# EasyEDA_Source.net
KiCad netlist of a schematic drawn in EasyEDA
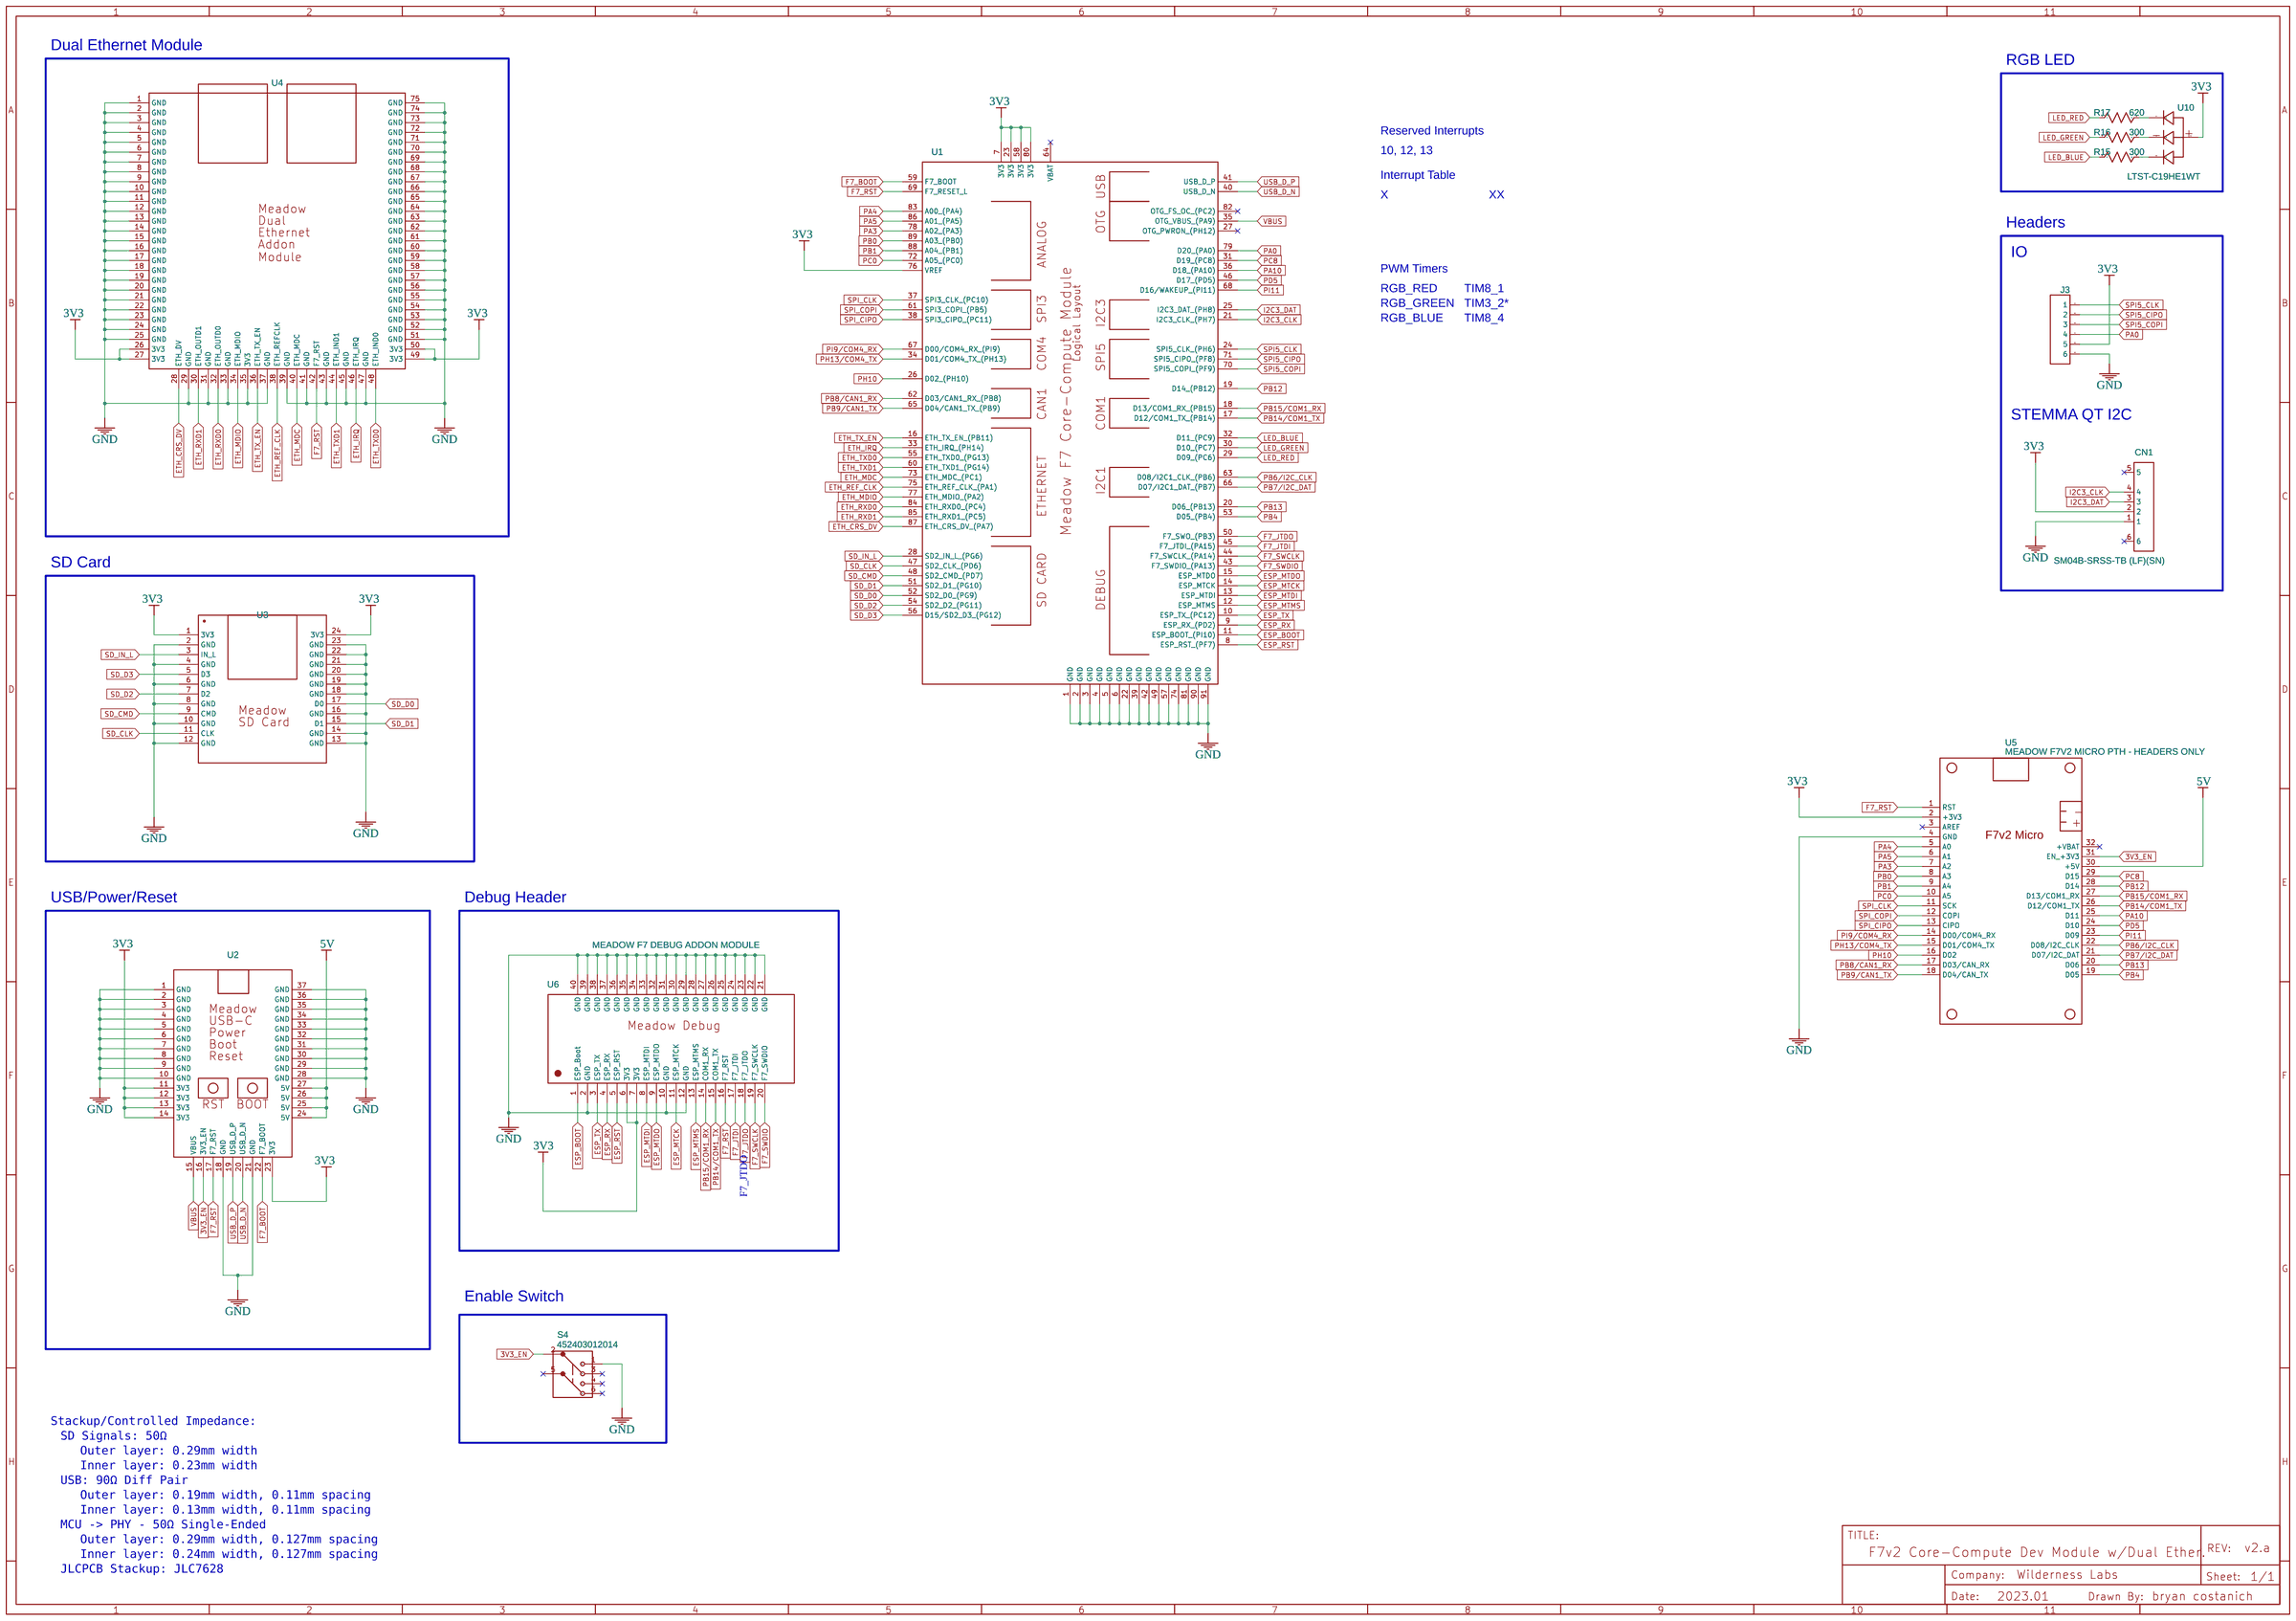
[diagram p0: schematic sheet]

(export (version "E")
  (design (tool "Eeschema 10.0.6"))
  (components
    (comp (ref "CN1")
      (value "SM04B-SRSS-TB (LF)(SN)")
      (fields (field (name "BOM_Supplier Part") "C160404"))
      (libsource (lib "") (part "SM04B-SRSS-TB (LF)(SN)"))
    )
    (comp (ref "J3")
      (value "HDR-M-2.54_1x6")
      (fields (field (name "BOM_Supplier Part") "C190819"))
      (libsource (lib "") (part "HDR-M-2.54_1x6"))
    )
    (comp (ref "R15")
      (value "300")
      (fields (field (name "BOM_Manufacturer Part") "RC0603FR-07300RL"))
      (libsource (lib "") (part "R_0603_US"))
    )
    (comp (ref "R16")
      (value "300")
      (fields (field (name "BOM_Manufacturer Part") "RC0603FR-07300RL"))
      (libsource (lib "") (part "R_0603_US"))
    )
    (comp (ref "R17")
      (value "620")
      (fields (field (name "BOM_Manufacturer Part") "RC0603FR-07620RL"))
      (libsource (lib "") (part "R_0603_US"))
    )
    (comp (ref "S4") (value "452403012014") (libsource (lib "") (part "452403012014")))
    (comp (ref "U1")
      (value "Meadow F7v2 Core-Compute Module - Logical")
      (libsource (lib "") (part "Meadow F7v2 Core-Compute Module - Logical"))
    )
    (comp (ref "U2")
      (value "Meadow Core-Compute USB-C, Power, Boot, and Reset Addon Module")
      (libsource (lib "") (part "Meadow Core-Compute USB-C, Power, Boot, and Reset Addon Module"))
    )
    (comp (ref "U3")
      (value "Meadow Core-Compute SD-Card Addon")
      (libsource (lib "") (part "Meadow Core-Compute SD-Card Addon"))
    )
    (comp (ref "U4")
      (value "MEADOW CORE-COMPUTE DUAL ETHERNET ADDON MODULE")
      (libsource (lib "") (part "MEADOW CORE-COMPUTE DUAL ETHERNET ADDON MODULE"))
    )
    (comp (ref "U5")
      (value "MEADOW F7V2 MICRO PTH - HEADERS ONLY")
      (fields
        (field (name "BOM_Manufacturer Part") "MEDF7DEV")
        (field (name "BOM_Supplier Part") "977-MEADOWF7MICRO")
      )
      (libsource (lib "") (part "MEADOW F7V2 MICRO PTH - HEADERS ONLY"))
    )
    (comp (ref "U6")
      (value "MEADOW F7 DEBUG ADDON MODULE")
      (libsource (lib "") (part "MEADOW F7 DEBUG ADDON MODULE"))
    )
    (comp (ref "U10")
      (value "LTST-C19HE1WT")
      (fields
        (field (name "BOM_Manufacturer Part") "LTST-C19HE1WT-H")
        (field (name "BOM_Supplier Part") "C427425")
      )
      (libsource (lib "") (part "LTST-C19HE1WT-H"))
    )
  )
  (nets
    (net (code "1") (name "3V3") (class "Default")
      (node (ref "CN1") (pin "2") (pinfunction "2_2") (pintype "unspecified"))
      (node (ref "J3") (pin "5") (pinfunction "5_5") (pintype "input"))
      (node (ref "U1") (pin "23") (pinfunction "3V3_23") (pintype "unspecified"))
      (node (ref "U1") (pin "58") (pinfunction "3V3_58") (pintype "passive"))
      (node (ref "U1") (pin "7") (pinfunction "3V3_7") (pintype "unspecified"))
      (node (ref "U1") (pin "76") (pinfunction "VREF_76") (pintype "input"))
      (node (ref "U1") (pin "80") (pinfunction "3V3_80") (pintype "unspecified"))
      (node (ref "U10") (pin "4") (pinfunction "A_4") (pintype "unspecified"))
      (node (ref "U2") (pin "11") (pinfunction "3V3_11") (pintype "unspecified"))
      (node (ref "U2") (pin "12") (pinfunction "3V3_12") (pintype "unspecified"))
      (node (ref "U2") (pin "13") (pinfunction "3V3_13") (pintype "unspecified"))
      (node (ref "U2") (pin "14") (pinfunction "3V3_14") (pintype "unspecified"))
      (node (ref "U2") (pin "23") (pinfunction "3V3_23") (pintype "passive"))
      (node (ref "U3") (pin "1") (pinfunction "3V3_1") (pintype "unspecified"))
      (node (ref "U3") (pin "24") (pinfunction "3V3_24") (pintype "passive"))
      (node (ref "U4") (pin "26") (pinfunction "3V3_26") (pintype "unspecified"))
      (node (ref "U4") (pin "27") (pinfunction "3V3_27") (pintype "unspecified"))
      (node (ref "U4") (pin "49") (pinfunction "3V3_49") (pintype "unspecified"))
      (node (ref "U4") (pin "50") (pinfunction "3V3_50") (pintype "unspecified"))
      (node (ref "U5") (pin "2") (pinfunction "+3V3_2") (pintype "passive"))
      (node (ref "U6") (pin "6") (pinfunction "3V3_6") (pintype "unspecified"))
      (node (ref "U6") (pin "7") (pinfunction "3V3_7") (pintype "unspecified"))
    )
    (net (code "2") (name "3V3_EN") (class "Default")
      (node (ref "S4") (pin "2") (pinfunction "1_2") (pintype "unspecified"))
      (node (ref "U2") (pin "16") (pinfunction "3V3_EN_16") (pintype "unspecified"))
      (node (ref "U5") (pin "31") (pinfunction "EN_+3V3_31") (pintype "unspecified"))
    )
    (net (code "3") (name "5V") (class "Default")
      (node (ref "U2") (pin "24") (pinfunction "5V_24") (pintype "passive"))
      (node (ref "U2") (pin "25") (pinfunction "5V_25") (pintype "passive"))
      (node (ref "U2") (pin "26") (pinfunction "5V_26") (pintype "passive"))
      (node (ref "U2") (pin "27") (pinfunction "5V_27") (pintype "passive"))
      (node (ref "U5") (pin "30") (pinfunction "+5V_30") (pintype "passive"))
    )
    (net (code "4") (name "ESP_BOOT") (class "Default")
      (node (ref "U1") (pin "11") (pinfunction "ESP_BOOT_(PI10)_11") (pintype "unspecified"))
      (node (ref "U6") (pin "1") (pinfunction "ESP_Boot_1") (pintype "unspecified"))
    )
    (net (code "5") (name "ESP_MTCK") (class "Default")
      (node (ref "U1") (pin "14") (pinfunction "ESP_MTCK_14") (pintype "unspecified"))
      (node (ref "U6") (pin "11") (pinfunction "ESP_MTCK_11") (pintype "unspecified"))
    )
    (net (code "6") (name "ESP_MTDI") (class "Default")
      (node (ref "U1") (pin "13") (pinfunction "ESP_MTDI_13") (pintype "unspecified"))
      (node (ref "U6") (pin "8") (pinfunction "ESP_MTDI_8") (pintype "unspecified"))
    )
    (net (code "7") (name "ESP_MTDO") (class "Default")
      (node (ref "U1") (pin "15") (pinfunction "ESP_MTDO_15") (pintype "unspecified"))
      (node (ref "U6") (pin "9") (pinfunction "ESP_MTDO_9") (pintype "unspecified"))
    )
    (net (code "8") (name "ESP_MTMS") (class "Default")
      (node (ref "U1") (pin "12") (pinfunction "ESP_MTMS_12") (pintype "unspecified"))
      (node (ref "U6") (pin "13") (pinfunction "ESP_MTMS_13") (pintype "unspecified"))
    )
    (net (code "9") (name "ESP_RST") (class "Default")
      (node (ref "U1") (pin "8") (pinfunction "ESP_RST_(PF7)_8") (pintype "unspecified"))
      (node (ref "U6") (pin "5") (pinfunction "ESP_RST_5") (pintype "unspecified"))
    )
    (net (code "10") (name "ESP_RX") (class "Default")
      (node (ref "U1") (pin "9") (pinfunction "ESP_RX_(PD2)_9") (pintype "unspecified"))
      (node (ref "U6") (pin "4") (pinfunction "ESP_RX_4") (pintype "unspecified"))
    )
    (net (code "11") (name "ESP_TX") (class "Default")
      (node (ref "U1") (pin "10") (pinfunction "ESP_TX_(PC12)_10") (pintype "unspecified"))
      (node (ref "U6") (pin "3") (pinfunction "ESP_TX_3") (pintype "unspecified"))
    )
    (net (code "12") (name "ETH_CRS_DV") (class "Default")
      (node (ref "U1") (pin "87") (pinfunction "ETH_CRS_DV_(PA7)_87") (pintype "unspecified"))
      (node (ref "U4") (pin "28") (pinfunction "ETH_DV_28") (pintype "unspecified"))
    )
    (net (code "13") (name "ETH_IRQ") (class "Default")
      (node (ref "U1") (pin "33") (pinfunction "ETH_IRQ_(PH14)_33") (pintype "unspecified"))
      (node (ref "U4") (pin "46") (pinfunction "ETH_IRQ_46") (pintype "unspecified"))
    )
    (net (code "14") (name "ETH_MDC") (class "Default")
      (node (ref "U1") (pin "73") (pinfunction "ETH_MDC_(PC1)_73") (pintype "unspecified"))
      (node (ref "U4") (pin "40") (pinfunction "ETH_MDC_40") (pintype "unspecified"))
    )
    (net (code "15") (name "ETH_MDIO") (class "Default")
      (node (ref "U1") (pin "77") (pinfunction "ETH_MDIO_(PA2)_77") (pintype "unspecified"))
      (node (ref "U4") (pin "34") (pinfunction "ETH_MDIO_34") (pintype "unspecified"))
    )
    (net (code "16") (name "ETH_REF_CLK") (class "Default")
      (node (ref "U1") (pin "75") (pinfunction "ETH_REF_CLK_(PA1)_75") (pintype "unspecified"))
      (node (ref "U4") (pin "38") (pinfunction "ETH_REFCLK_38") (pintype "unspecified"))
    )
    (net (code "17") (name "ETH_RXD0") (class "Default")
      (node (ref "U1") (pin "84") (pinfunction "ETH_RXD0_(PC4)_84") (pintype "unspecified"))
      (node (ref "U4") (pin "32") (pinfunction "ETH_OUTD0_32") (pintype "unspecified"))
    )
    (net (code "18") (name "ETH_RXD1") (class "Default")
      (node (ref "U1") (pin "85") (pinfunction "ETH_RXD1_(PC5)_85") (pintype "unspecified"))
      (node (ref "U4") (pin "30") (pinfunction "ETH_OUTD1_30") (pintype "unspecified"))
    )
    (net (code "19") (name "ETH_TXD0") (class "Default")
      (node (ref "U1") (pin "55") (pinfunction "ETH_TXD0_(PG13)_55") (pintype "unspecified"))
      (node (ref "U4") (pin "48") (pinfunction "ETH_IND0_48") (pintype "unspecified"))
    )
    (net (code "20") (name "ETH_TXD1") (class "Default")
      (node (ref "U1") (pin "60") (pinfunction "ETH_TXD1_(PG14)_60") (pintype "unspecified"))
      (node (ref "U4") (pin "44") (pinfunction "ETH_IND1_44") (pintype "unspecified"))
    )
    (net (code "21") (name "ETH_TX_EN") (class "Default")
      (node (ref "U1") (pin "16") (pinfunction "ETH_TX_EN_(PB11)_16") (pintype "unspecified"))
      (node (ref "U4") (pin "36") (pinfunction "ETH_TX_EN_36") (pintype "unspecified"))
    )
    (net (code "22") (name "F7_BOOT") (class "Default")
      (node (ref "U1") (pin "59") (pinfunction "F7_BOOT_59") (pintype "unspecified"))
      (node (ref "U2") (pin "22") (pinfunction "F7_BOOT_22") (pintype "unspecified"))
    )
    (net (code "23") (name "F7_JTDI") (class "Default")
      (node (ref "U1") (pin "45") (pinfunction "F7_JTDI_(PA15)_45") (pintype "unspecified"))
      (node (ref "U6") (pin "17") (pinfunction "F7_JTDI_17") (pintype "unspecified"))
    )
    (net (code "24") (name "F7_JTDO") (class "Default")
      (node (ref "U1") (pin "50") (pinfunction "F7_SWO_(PB3)_50") (pintype "unspecified"))
      (node (ref "U6") (pin "18") (pinfunction "F7_JTDO_18") (pintype "unspecified"))
    )
    (net (code "25") (name "F7_RST") (class "Default")
      (node (ref "U1") (pin "69") (pinfunction "F7_RESET_L_69") (pintype "unspecified"))
      (node (ref "U2") (pin "17") (pinfunction "F7_RST_17") (pintype "unspecified"))
      (node (ref "U4") (pin "42") (pinfunction "F7_RST_42") (pintype "unspecified"))
      (node (ref "U5") (pin "1") (pinfunction "RST_1") (pintype "input"))
      (node (ref "U6") (pin "16") (pinfunction "F7_RST_16") (pintype "unspecified"))
    )
    (net (code "26") (name "F7_SWCLK") (class "Default")
      (node (ref "U1") (pin "44") (pinfunction "F7_SWCLK_(PA14)_44") (pintype "unspecified"))
      (node (ref "U6") (pin "19") (pinfunction "F7_SWCLK_19") (pintype "unspecified"))
    )
    (net (code "27") (name "F7_SWDIO") (class "Default")
      (node (ref "U1") (pin "43") (pinfunction "F7_SWDIO_(PA13)_43") (pintype "unspecified"))
      (node (ref "U6") (pin "20") (pinfunction "F7_SWDIO_20") (pintype "unspecified"))
    )
    (net (code "28") (name "GND") (class "Default")
      (node (ref "CN1") (pin "1") (pinfunction "1_1") (pintype "unspecified"))
      (node (ref "J3") (pin "6") (pinfunction "6_6") (pintype "input"))
      (node (ref "S4") (pin "1") (pinfunction "1_1") (pintype "unspecified"))
      (node (ref "U1") (pin "1") (pinfunction "GND_1") (pintype "passive"))
      (node (ref "U1") (pin "2") (pinfunction "GND_2") (pintype "passive"))
      (node (ref "U1") (pin "22") (pinfunction "GND_22") (pintype "passive"))
      (node (ref "U1") (pin "3") (pinfunction "GND_3") (pintype "passive"))
      (node (ref "U1") (pin "39") (pinfunction "GND_39") (pintype "passive"))
      (node (ref "U1") (pin "4") (pinfunction "GND_4") (pintype "passive"))
      (node (ref "U1") (pin "42") (pinfunction "GND_42") (pintype "passive"))
      (node (ref "U1") (pin "49") (pinfunction "GND_49") (pintype "passive"))
      (node (ref "U1") (pin "5") (pinfunction "GND_5") (pintype "passive"))
      (node (ref "U1") (pin "57") (pinfunction "GND_57") (pintype "passive"))
      (node (ref "U1") (pin "6") (pinfunction "GND_6") (pintype "passive"))
      (node (ref "U1") (pin "74") (pinfunction "GND_74") (pintype "passive"))
      (node (ref "U1") (pin "81") (pinfunction "GND_81") (pintype "passive"))
      (node (ref "U1") (pin "90") (pinfunction "GND_90") (pintype "passive"))
      (node (ref "U1") (pin "91") (pinfunction "GND_91") (pintype "passive"))
      (node (ref "U2") (pin "1") (pinfunction "GND_1") (pintype "unspecified"))
      (node (ref "U2") (pin "10") (pinfunction "GND_10") (pintype "unspecified"))
      (node (ref "U2") (pin "18") (pinfunction "GND_18") (pintype "unspecified"))
      (node (ref "U2") (pin "2") (pinfunction "GND_2") (pintype "unspecified"))
      (node (ref "U2") (pin "21") (pinfunction "GND_21") (pintype "unspecified"))
      (node (ref "U2") (pin "28") (pinfunction "GND_28") (pintype "unspecified"))
      (node (ref "U2") (pin "29") (pinfunction "GND_29") (pintype "unspecified"))
      (node (ref "U2") (pin "3") (pinfunction "GND_3") (pintype "unspecified"))
      (node (ref "U2") (pin "30") (pinfunction "GND_30") (pintype "unspecified"))
      (node (ref "U2") (pin "31") (pinfunction "GND_31") (pintype "unspecified"))
      (node (ref "U2") (pin "32") (pinfunction "GND_32") (pintype "unspecified"))
      (node (ref "U2") (pin "33") (pinfunction "GND_33") (pintype "unspecified"))
      (node (ref "U2") (pin "34") (pinfunction "GND_34") (pintype "unspecified"))
      (node (ref "U2") (pin "35") (pinfunction "GND_35") (pintype "unspecified"))
      (node (ref "U2") (pin "36") (pinfunction "GND_36") (pintype "unspecified"))
      (node (ref "U2") (pin "37") (pinfunction "GND_37") (pintype "unspecified"))
      (node (ref "U2") (pin "4") (pinfunction "GND_4") (pintype "unspecified"))
      (node (ref "U2") (pin "5") (pinfunction "GND_5") (pintype "unspecified"))
      (node (ref "U2") (pin "6") (pinfunction "GND_6") (pintype "unspecified"))
      (node (ref "U2") (pin "7") (pinfunction "GND_7") (pintype "unspecified"))
      (node (ref "U2") (pin "8") (pinfunction "GND_8") (pintype "unspecified"))
      (node (ref "U2") (pin "9") (pinfunction "GND_9") (pintype "unspecified"))
      (node (ref "U3") (pin "10") (pinfunction "GND_10") (pintype "unspecified"))
      (node (ref "U3") (pin "12") (pinfunction "GND_12") (pintype "unspecified"))
      (node (ref "U3") (pin "13") (pinfunction "GND_13") (pintype "unspecified"))
      (node (ref "U3") (pin "14") (pinfunction "GND_14") (pintype "unspecified"))
      (node (ref "U3") (pin "16") (pinfunction "GND_16") (pintype "passive"))
      (node (ref "U3") (pin "18") (pinfunction "GND_18") (pintype "passive"))
      (node (ref "U3") (pin "19") (pinfunction "GND_19") (pintype "passive"))
      (node (ref "U3") (pin "2") (pinfunction "GND_2") (pintype "unspecified"))
      (node (ref "U3") (pin "20") (pinfunction "GND_20") (pintype "passive"))
      (node (ref "U3") (pin "21") (pinfunction "GND_21") (pintype "passive"))
      (node (ref "U3") (pin "22") (pinfunction "GND_22") (pintype "passive"))
      (node (ref "U3") (pin "23") (pinfunction "GND_23") (pintype "passive"))
      (node (ref "U3") (pin "4") (pinfunction "GND_4") (pintype "unspecified"))
      (node (ref "U3") (pin "6") (pinfunction "GND_6") (pintype "unspecified"))
      (node (ref "U3") (pin "8") (pinfunction "GND_8") (pintype "unspecified"))
      (node (ref "U4") (pin "1") (pinfunction "GND_1") (pintype "unspecified"))
      (node (ref "U4") (pin "10") (pinfunction "GND_10") (pintype "unspecified"))
      (node (ref "U4") (pin "11") (pinfunction "GND_11") (pintype "unspecified"))
      (node (ref "U4") (pin "12") (pinfunction "GND_12") (pintype "unspecified"))
      (node (ref "U4") (pin "13") (pinfunction "GND_13") (pintype "unspecified"))
      (node (ref "U4") (pin "14") (pinfunction "GND_14") (pintype "unspecified"))
      (node (ref "U4") (pin "15") (pinfunction "GND_15") (pintype "unspecified"))
      (node (ref "U4") (pin "16") (pinfunction "GND_16") (pintype "unspecified"))
      (node (ref "U4") (pin "17") (pinfunction "GND_17") (pintype "unspecified"))
      (node (ref "U4") (pin "18") (pinfunction "GND_18") (pintype "unspecified"))
      (node (ref "U4") (pin "19") (pinfunction "GND_19") (pintype "unspecified"))
      (node (ref "U4") (pin "2") (pinfunction "GND_2") (pintype "unspecified"))
      (node (ref "U4") (pin "20") (pinfunction "GND_20") (pintype "unspecified"))
      (node (ref "U4") (pin "21") (pinfunction "GND_21") (pintype "unspecified"))
      (node (ref "U4") (pin "22") (pinfunction "GND_22") (pintype "unspecified"))
      (node (ref "U4") (pin "23") (pinfunction "GND_23") (pintype "unspecified"))
      (node (ref "U4") (pin "24") (pinfunction "GND_24") (pintype "unspecified"))
      (node (ref "U4") (pin "25") (pinfunction "GND_25") (pintype "unspecified"))
      (node (ref "U4") (pin "29") (pinfunction "GND_29") (pintype "unspecified"))
      (node (ref "U4") (pin "3") (pinfunction "GND_3") (pintype "unspecified"))
      (node (ref "U4") (pin "31") (pinfunction "GND_31") (pintype "unspecified"))
      (node (ref "U4") (pin "33") (pinfunction "GND_33") (pintype "unspecified"))
      (node (ref "U4") (pin "35") (pinfunction "3V3_35") (pintype "unspecified"))
      (node (ref "U4") (pin "37") (pinfunction "GND_37") (pintype "unspecified"))
      (node (ref "U4") (pin "39") (pinfunction "GND_39") (pintype "unspecified"))
      (node (ref "U4") (pin "4") (pinfunction "GND_4") (pintype "unspecified"))
      (node (ref "U4") (pin "41") (pinfunction "GND_41") (pintype "unspecified"))
      (node (ref "U4") (pin "43") (pinfunction "GND_43") (pintype "unspecified"))
      (node (ref "U4") (pin "45") (pinfunction "GND_45") (pintype "unspecified"))
      (node (ref "U4") (pin "47") (pinfunction "GND_47") (pintype "unspecified"))
      (node (ref "U4") (pin "5") (pinfunction "GND_5") (pintype "unspecified"))
      (node (ref "U4") (pin "51") (pinfunction "GND_51") (pintype "unspecified"))
      (node (ref "U4") (pin "52") (pinfunction "GND_52") (pintype "unspecified"))
      (node (ref "U4") (pin "53") (pinfunction "GND_53") (pintype "unspecified"))
      (node (ref "U4") (pin "54") (pinfunction "GND_54") (pintype "unspecified"))
      (node (ref "U4") (pin "55") (pinfunction "GND_55") (pintype "unspecified"))
      (node (ref "U4") (pin "56") (pinfunction "GND_56") (pintype "unspecified"))
      (node (ref "U4") (pin "57") (pinfunction "GND_57") (pintype "unspecified"))
      (node (ref "U4") (pin "58") (pinfunction "GND_58") (pintype "unspecified"))
      (node (ref "U4") (pin "59") (pinfunction "GND_59") (pintype "unspecified"))
      (node (ref "U4") (pin "6") (pinfunction "GND_6") (pintype "unspecified"))
      (node (ref "U4") (pin "60") (pinfunction "GND_60") (pintype "unspecified"))
      (node (ref "U4") (pin "61") (pinfunction "GND_61") (pintype "unspecified"))
      (node (ref "U4") (pin "62") (pinfunction "GND_62") (pintype "unspecified"))
      (node (ref "U4") (pin "63") (pinfunction "GND_63") (pintype "unspecified"))
      (node (ref "U4") (pin "64") (pinfunction "GND_64") (pintype "unspecified"))
      (node (ref "U4") (pin "65") (pinfunction "GND_65") (pintype "unspecified"))
      (node (ref "U4") (pin "66") (pinfunction "GND_66") (pintype "unspecified"))
      (node (ref "U4") (pin "67") (pinfunction "GND_67") (pintype "unspecified"))
      (node (ref "U4") (pin "68") (pinfunction "GND_68") (pintype "unspecified"))
      (node (ref "U4") (pin "69") (pinfunction "GND_69") (pintype "unspecified"))
      (node (ref "U4") (pin "7") (pinfunction "GND_7") (pintype "unspecified"))
      (node (ref "U4") (pin "70") (pinfunction "GND_70") (pintype "unspecified"))
      (node (ref "U4") (pin "71") (pinfunction "GND_71") (pintype "unspecified"))
      (node (ref "U4") (pin "72") (pinfunction "GND_72") (pintype "unspecified"))
      (node (ref "U4") (pin "73") (pinfunction "GND_73") (pintype "unspecified"))
      (node (ref "U4") (pin "74") (pinfunction "GND_74") (pintype "unspecified"))
      (node (ref "U4") (pin "75") (pinfunction "GND_75") (pintype "unspecified"))
      (node (ref "U4") (pin "8") (pinfunction "GND_8") (pintype "unspecified"))
      (node (ref "U4") (pin "9") (pinfunction "GND_9") (pintype "unspecified"))
      (node (ref "U5") (pin "4") (pinfunction "GND_4") (pintype "passive"))
      (node (ref "U6") (pin "10") (pinfunction "GND_10") (pintype "unspecified"))
      (node (ref "U6") (pin "12") (pinfunction "GND_12") (pintype "unspecified"))
      (node (ref "U6") (pin "2") (pinfunction "GND_2") (pintype "unspecified"))
      (node (ref "U6") (pin "21") (pinfunction "GND_21") (pintype "unspecified"))
      (node (ref "U6") (pin "22") (pinfunction "GND_22") (pintype "unspecified"))
      (node (ref "U6") (pin "23") (pinfunction "GND_23") (pintype "unspecified"))
      (node (ref "U6") (pin "24") (pinfunction "GND_24") (pintype "unspecified"))
      (node (ref "U6") (pin "25") (pinfunction "GND_25") (pintype "unspecified"))
      (node (ref "U6") (pin "26") (pinfunction "GND_26") (pintype "unspecified"))
      (node (ref "U6") (pin "27") (pinfunction "GND_27") (pintype "unspecified"))
      (node (ref "U6") (pin "28") (pinfunction "GND_28") (pintype "unspecified"))
      (node (ref "U6") (pin "29") (pinfunction "GND_29") (pintype "unspecified"))
      (node (ref "U6") (pin "30") (pinfunction "GND_30") (pintype "unspecified"))
      (node (ref "U6") (pin "31") (pinfunction "GND_31") (pintype "unspecified"))
      (node (ref "U6") (pin "32") (pinfunction "GND_32") (pintype "unspecified"))
      (node (ref "U6") (pin "33") (pinfunction "GND_33") (pintype "unspecified"))
      (node (ref "U6") (pin "34") (pinfunction "GND_34") (pintype "unspecified"))
      (node (ref "U6") (pin "35") (pinfunction "GND_35") (pintype "unspecified"))
      (node (ref "U6") (pin "36") (pinfunction "GND_36") (pintype "unspecified"))
      (node (ref "U6") (pin "37") (pinfunction "GND_37") (pintype "unspecified"))
      (node (ref "U6") (pin "38") (pinfunction "GND_38") (pintype "unspecified"))
      (node (ref "U6") (pin "39") (pinfunction "GND_39") (pintype "unspecified"))
      (node (ref "U6") (pin "40") (pinfunction "GND_40") (pintype "unspecified"))
    )
    (net (code "29") (name "I2C3_CLK") (class "Default")
      (node (ref "CN1") (pin "4") (pinfunction "4_4") (pintype "unspecified"))
      (node (ref "U1") (pin "21") (pinfunction "I2C3_CLK_(PH7)_21") (pintype "unspecified"))
    )
    (net (code "30") (name "I2C3_DAT") (class "Default")
      (node (ref "CN1") (pin "3") (pinfunction "3_3") (pintype "unspecified"))
      (node (ref "U1") (pin "25") (pinfunction "I2C3_DAT_(PH8)_25") (pintype "unspecified"))
    )
    (net (code "31") (name "LED_BLUE") (class "Default")
      (node (ref "R15") (pin "1") (pinfunction "1_1") (pintype "unspecified"))
      (node (ref "U1") (pin "32") (pinfunction "D11_(PC9)_32") (pintype "unspecified"))
    )
    (net (code "32") (name "LED_GREEN") (class "Default")
      (node (ref "R16") (pin "1") (pinfunction "1_1") (pintype "unspecified"))
      (node (ref "U1") (pin "30") (pinfunction "D10_(PC7)_30") (pintype "unspecified"))
    )
    (net (code "33") (name "LED_RED") (class "Default")
      (node (ref "R17") (pin "1") (pinfunction "1_1") (pintype "unspecified"))
      (node (ref "U1") (pin "29") (pinfunction "D09_(PC6)_29") (pintype "unspecified"))
    )
    (net (code "34") (name "Net-(U10-C1)") (class "Default")
      (node (ref "R17") (pin "2") (pinfunction "2_2") (pintype "unspecified"))
      (node (ref "U10") (pin "1") (pinfunction "C1_1") (pintype "unspecified"))
    )
    (net (code "35") (name "Net-(U10-C2)") (class "Default")
      (node (ref "R16") (pin "2") (pinfunction "2_2") (pintype "unspecified"))
      (node (ref "U10") (pin "2") (pinfunction "C2_2") (pintype "unspecified"))
    )
    (net (code "36") (name "Net-(U10-C3)") (class "Default")
      (node (ref "R15") (pin "2") (pinfunction "2_2") (pintype "unspecified"))
      (node (ref "U10") (pin "3") (pinfunction "C3_3") (pintype "unspecified"))
    )
    (net (code "37") (name "PA0") (class "Default")
      (node (ref "J3") (pin "4") (pinfunction "4_4") (pintype "input"))
      (node (ref "U1") (pin "79") (pinfunction "D20_(PA0)_79") (pintype "unspecified"))
    )
    (net (code "38") (name "PA3") (class "Default")
      (node (ref "U1") (pin "78") (pinfunction "A02_(PA3)_78") (pintype "unspecified"))
      (node (ref "U5") (pin "7") (pinfunction "A2_7") (pintype "bidirectional"))
    )
    (net (code "39") (name "PA4") (class "Default")
      (node (ref "U1") (pin "83") (pinfunction "A00_(PA4)_83") (pintype "unspecified"))
      (node (ref "U5") (pin "5") (pinfunction "A0_5") (pintype "bidirectional"))
    )
    (net (code "40") (name "PA5") (class "Default")
      (node (ref "U1") (pin "86") (pinfunction "A01_(PA5)_86") (pintype "unspecified"))
      (node (ref "U5") (pin "6") (pinfunction "A1_6") (pintype "bidirectional"))
    )
    (net (code "41") (name "PA10") (class "Default")
      (node (ref "U1") (pin "36") (pinfunction "D18_(PA10)_36") (pintype "unspecified"))
      (node (ref "U5") (pin "25") (pinfunction "D11_25") (pintype "bidirectional"))
    )
    (net (code "42") (name "PB0") (class "Default")
      (node (ref "U1") (pin "89") (pinfunction "A03_(PB0)_89") (pintype "unspecified"))
      (node (ref "U5") (pin "8") (pinfunction "A3_8") (pintype "bidirectional"))
    )
    (net (code "43") (name "PB1") (class "Default")
      (node (ref "U1") (pin "88") (pinfunction "A04_(PB1)_88") (pintype "unspecified"))
      (node (ref "U5") (pin "9") (pinfunction "A4_9") (pintype "bidirectional"))
    )
    (net (code "44") (name "PB4") (class "Default")
      (node (ref "U1") (pin "53") (pinfunction "D05_(PB4)_53") (pintype "unspecified"))
      (node (ref "U5") (pin "19") (pinfunction "D05_19") (pintype "bidirectional"))
    )
    (net (code "45") (name "PB6{slash}I2C_CLK") (class "Default")
      (node (ref "U1") (pin "63") (pinfunction "D08/I2C1_CLK_(PB6)_63") (pintype "unspecified"))
      (node (ref "U5") (pin "22") (pinfunction "D08/I2C_CLK_22") (pintype "bidirectional"))
    )
    (net (code "46") (name "PB7{slash}I2C_DAT") (class "Default")
      (node (ref "U1") (pin "66") (pinfunction "D07/I2C1_DAT_(PB7)_66") (pintype "unspecified"))
      (node (ref "U5") (pin "21") (pinfunction "D07/I2C_DAT_21") (pintype "bidirectional"))
    )
    (net (code "47") (name "PB8{slash}CAN1_RX") (class "Default")
      (node (ref "U1") (pin "62") (pinfunction "D03/CAN1_RX_(PB8)_62") (pintype "unspecified"))
      (node (ref "U5") (pin "17") (pinfunction "D03/CAN_RX_17") (pintype "bidirectional"))
    )
    (net (code "48") (name "PB9{slash}CAN1_TX") (class "Default")
      (node (ref "U1") (pin "65") (pinfunction "D04/CAN1_TX_(PB9)_65") (pintype "unspecified"))
      (node (ref "U5") (pin "18") (pinfunction "D04/CAN_TX_18") (pintype "bidirectional"))
    )
    (net (code "49") (name "PB12") (class "Default")
      (node (ref "U1") (pin "19") (pinfunction "D14_(PB12)_19") (pintype "unspecified"))
      (node (ref "U5") (pin "28") (pinfunction "D14_28") (pintype "bidirectional"))
    )
    (net (code "50") (name "PB13") (class "Default")
      (node (ref "U1") (pin "20") (pinfunction "D06_(PB13)_20") (pintype "unspecified"))
      (node (ref "U5") (pin "20") (pinfunction "D06_20") (pintype "bidirectional"))
    )
    (net (code "51") (name "PB14{slash}COM1_TX") (class "Default")
      (node (ref "U1") (pin "17") (pinfunction "D12/COM1_TX_(PB14)_17") (pintype "unspecified"))
      (node (ref "U5") (pin "26") (pinfunction "D12/COM1_TX_26") (pintype "bidirectional"))
      (node (ref "U6") (pin "15") (pinfunction "COM1_TX_15") (pintype "unspecified"))
    )
    (net (code "52") (name "PB15{slash}COM1_RX") (class "Default")
      (node (ref "U1") (pin "18") (pinfunction "D13/COM1_RX_(PB15)_18") (pintype "unspecified"))
      (node (ref "U5") (pin "27") (pinfunction "D13/COM1_RX_27") (pintype "bidirectional"))
      (node (ref "U6") (pin "14") (pinfunction "COM1_RX_14") (pintype "unspecified"))
    )
    (net (code "53") (name "PC0") (class "Default")
      (node (ref "U1") (pin "72") (pinfunction "A05_(PC0)_72") (pintype "unspecified"))
      (node (ref "U5") (pin "10") (pinfunction "A5_10") (pintype "bidirectional"))
    )
    (net (code "54") (name "PC8") (class "Default")
      (node (ref "U1") (pin "31") (pinfunction "D19_(PC8)_31") (pintype "unspecified"))
      (node (ref "U5") (pin "29") (pinfunction "D15_29") (pintype "bidirectional"))
    )
    (net (code "55") (name "PD5") (class "Default")
      (node (ref "U1") (pin "46") (pinfunction "D17_(PD5)_46") (pintype "unspecified"))
      (node (ref "U5") (pin "24") (pinfunction "D10_24") (pintype "bidirectional"))
    )
    (net (code "56") (name "PH10") (class "Default")
      (node (ref "U1") (pin "26") (pinfunction "D02_(PH10)_26") (pintype "unspecified"))
      (node (ref "U5") (pin "16") (pinfunction "D02_16") (pintype "bidirectional"))
    )
    (net (code "57") (name "PH13{slash}COM4_TX") (class "Default")
      (node (ref "U1") (pin "34") (pinfunction "D01/COM4_TX_(PH13)_34") (pintype "unspecified"))
      (node (ref "U5") (pin "15") (pinfunction "D01/COM4_TX_15") (pintype "bidirectional"))
    )
    (net (code "58") (name "PI9{slash}COM4_RX") (class "Default")
      (node (ref "U1") (pin "67") (pinfunction "D00/COM4_RX_(PI9)_67") (pintype "unspecified"))
      (node (ref "U5") (pin "14") (pinfunction "D00/COM4_RX_14") (pintype "bidirectional"))
    )
    (net (code "59") (name "PI11") (class "Default")
      (node (ref "U1") (pin "68") (pinfunction "D16/WAKEUP_(PI11)_68") (pintype "unspecified"))
      (node (ref "U5") (pin "23") (pinfunction "D09_23") (pintype "bidirectional"))
    )
    (net (code "60") (name "SD_CLK") (class "Default")
      (node (ref "U1") (pin "47") (pinfunction "SD2_CLK_(PD6)_47") (pintype "unspecified"))
      (node (ref "U3") (pin "11") (pinfunction "CLK_11") (pintype "unspecified"))
    )
    (net (code "61") (name "SD_CMD") (class "Default")
      (node (ref "U1") (pin "48") (pinfunction "SD2_CMD_(PD7)_48") (pintype "unspecified"))
      (node (ref "U3") (pin "9") (pinfunction "CMD_9") (pintype "unspecified"))
    )
    (net (code "62") (name "SD_D0") (class "Default")
      (node (ref "U1") (pin "52") (pinfunction "SD2_D0_(PG9)_52") (pintype "unspecified"))
      (node (ref "U3") (pin "17") (pinfunction "D0_17") (pintype "passive"))
    )
    (net (code "63") (name "SD_D1") (class "Default")
      (node (ref "U1") (pin "51") (pinfunction "SD2_D1_(PG10)_51") (pintype "unspecified"))
      (node (ref "U3") (pin "15") (pinfunction "D1_15") (pintype "unspecified"))
    )
    (net (code "64") (name "SD_D2") (class "Default")
      (node (ref "U1") (pin "54") (pinfunction "SD2_D2_(PG11)_54") (pintype "unspecified"))
      (node (ref "U3") (pin "7") (pinfunction "D2_7") (pintype "unspecified"))
    )
    (net (code "65") (name "SD_D3") (class "Default")
      (node (ref "U1") (pin "56") (pinfunction "D15/SD2_D3_(PG12)_56") (pintype "unspecified"))
      (node (ref "U3") (pin "5") (pinfunction "D3_5") (pintype "unspecified"))
    )
    (net (code "66") (name "SD_IN_L") (class "Default")
      (node (ref "U1") (pin "28") (pinfunction "SD2_IN_L_(PG6)_28") (pintype "unspecified"))
      (node (ref "U3") (pin "3") (pinfunction "IN_L_3") (pintype "unspecified"))
    )
    (net (code "67") (name "SPI5_CIPO") (class "Default")
      (node (ref "J3") (pin "2") (pinfunction "2_2") (pintype "input"))
      (node (ref "U1") (pin "71") (pinfunction "SPI5_CIPO_(PF8)_71") (pintype "unspecified"))
    )
    (net (code "68") (name "SPI5_CLK") (class "Default")
      (node (ref "J3") (pin "1") (pinfunction "1_1") (pintype "input"))
      (node (ref "U1") (pin "24") (pinfunction "SPI5_CLK_(PH6)_24") (pintype "unspecified"))
    )
    (net (code "69") (name "SPI5_COPI") (class "Default")
      (node (ref "J3") (pin "3") (pinfunction "3_3") (pintype "input"))
      (node (ref "U1") (pin "70") (pinfunction "SPI5_COPI_(PF9)_70") (pintype "unspecified"))
    )
    (net (code "70") (name "SPI_CIPO") (class "Default")
      (node (ref "U1") (pin "38") (pinfunction "SPI3_CIPO_(PC11)_38") (pintype "unspecified"))
      (node (ref "U5") (pin "13") (pinfunction "CIPO_13") (pintype "bidirectional"))
    )
    (net (code "71") (name "SPI_CLK") (class "Default")
      (node (ref "U1") (pin "37") (pinfunction "SPI3_CLK_(PC10)_37") (pintype "unspecified"))
      (node (ref "U5") (pin "11") (pinfunction "SCK_11") (pintype "bidirectional"))
    )
    (net (code "72") (name "SPI_COPI") (class "Default")
      (node (ref "U1") (pin "61") (pinfunction "SPI3_COPI_(PB5)_61") (pintype "unspecified"))
      (node (ref "U5") (pin "12") (pinfunction "COPI_12") (pintype "bidirectional"))
    )
    (net (code "73") (name "USB_D_N") (class "Default")
      (node (ref "U1") (pin "40") (pinfunction "USB_D_N_40") (pintype "unspecified"))
      (node (ref "U2") (pin "20") (pinfunction "USB_D_N_20") (pintype "unspecified"))
    )
    (net (code "74") (name "USB_D_P") (class "Default")
      (node (ref "U1") (pin "41") (pinfunction "USB_D_P_41") (pintype "unspecified"))
      (node (ref "U2") (pin "19") (pinfunction "USB_D_P_19") (pintype "unspecified"))
    )
    (net (code "75") (name "VBUS") (class "Default")
      (node (ref "U1") (pin "35") (pinfunction "OTG_VBUS_(PA9)_35") (pintype "unspecified"))
      (node (ref "U2") (pin "15") (pinfunction "VBUS_15") (pintype "unspecified"))
    )
    (net (code "76") (name "unconnected-(CN1-Pad5)") (class "Default")
      (node (ref "CN1") (pin "5") (pinfunction "5_5") (pintype "unspecified+no_connect"))
    )
    (net (code "77") (name "unconnected-(CN1-Pad6)") (class "Default")
      (node (ref "CN1") (pin "6") (pinfunction "6_6") (pintype "unspecified+no_connect"))
    )
    (net (code "78") (name "unconnected-(S4-1-Pad3)") (class "Default")
      (node (ref "S4") (pin "3") (pinfunction "1_3") (pintype "unspecified+no_connect"))
    )
    (net (code "79") (name "unconnected-(S4-1-Pad4)") (class "Default")
      (node (ref "S4") (pin "4") (pinfunction "1_4") (pintype "unspecified+no_connect"))
    )
    (net (code "80") (name "unconnected-(S4-1-Pad6)") (class "Default")
      (node (ref "S4") (pin "6") (pinfunction "1_6") (pintype "unspecified+no_connect"))
    )
    (net (code "81") (name "unconnected-(S4-2-Pad5)") (class "Default")
      (node (ref "S4") (pin "5") (pinfunction "2_5") (pintype "unspecified+no_connect"))
    )
    (net (code "82") (name "unconnected-(U1-OTG_FS_OC_(PC2)-Pad82)") (class "Default")
      (node (ref "U1") (pin "82") (pinfunction "OTG_FS_OC_(PC2)_82") (pintype "unspecified+no_connect"))
    )
    (net (code "83") (name "unconnected-(U1-OTG_PWRON_(PH12)-Pad27)") (class "Default")
      (node (ref "U1") (pin "27") (pinfunction "OTG_PWRON_(PH12)_27") (pintype "unspecified+no_connect"))
    )
    (net (code "84") (name "unconnected-(U1-VBAT-Pad64)") (class "Default")
      (node (ref "U1") (pin "64") (pinfunction "VBAT_64") (pintype "input+no_connect"))
    )
    (net (code "85") (name "unconnected-(U5-+VBAT-Pad32)") (class "Default")
      (node (ref "U5") (pin "32") (pinfunction "+VBAT_32") (pintype "passive+no_connect"))
    )
    (net (code "86") (name "unconnected-(U5-AREF-Pad3)") (class "Default")
      (node (ref "U5") (pin "3") (pinfunction "AREF_3") (pintype "input+no_connect"))
    )
  )
)
